# Accelerometer.net
KiCad netlist of a schematic drawn in Altium Designer
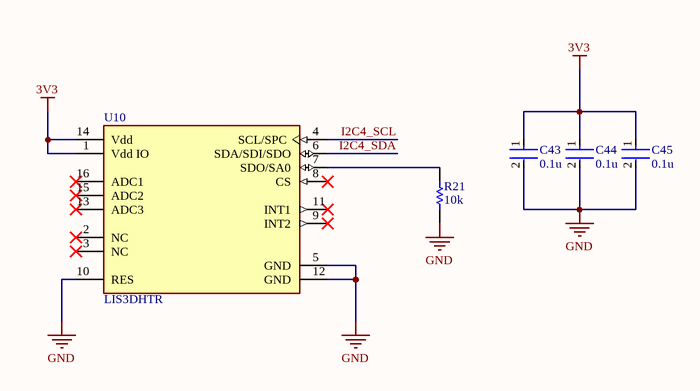
[diagram p0: Accelerometer.SchDoc]

(export (version "E")
  (design (tool "Eeschema 10.0.6"))
  (components
    (comp (ref "C43")
      (value "0.1u")
      (footprint "FP-C0603C-CF-MFG")
      (description "CAP CER 0.1UF 50V X7R 0603")
      (fields (field (name "TOLERANCE") "0.1") (field (name "MANUFACTURER") "KEMET"))
      (libsource (lib "Altium Content Vault") (part "b4654b650e69147ec39a6b967a45e02"))
    )
    (comp (ref "C44")
      (value "0.1u")
      (footprint "FP-C0603C-CF-MFG")
      (description "CAP CER 0.1UF 50V X7R 0603")
      (fields (field (name "TOLERANCE") "0.1") (field (name "MANUFACTURER") "KEMET"))
      (libsource (lib "Altium Content Vault") (part "b4654b650e69147ec39a6b967a45e02"))
    )
    (comp (ref "C45")
      (value "0.1u")
      (footprint "FP-C0603C-CF-MFG")
      (description "CAP CER 0.1UF 50V X7R 0603")
      (fields (field (name "TOLERANCE") "0.1") (field (name "MANUFACTURER") "KEMET"))
      (libsource (lib "Altium Content Vault") (part "b4654b650e69147ec39a6b967a45e02"))
    )
    (comp (ref "R21")
      (value "10k")
      (footprint "RESC1609X50X30NL8T20")
      (description "Chip Resistor, 10 KOhm, +/- 1%, 100 mW, -55 to 155 degC, 0603 (1608 Metric), RoHS, Tape and Reel")
      (fields (field (name "MANUFACTURER") "Vishay Semiconductor"))
      (libsource (lib "Altium Content Vault") (part "RES-2"))
    )
    (comp (ref "U10")
      (value "LIS3DHTR")
      (footprint "FP-LGA-16-7983231-MFG")
      (description "ACCEL 2-16G I2C/SPI 16LGA")
      (libsource (lib "Altium Content Vault") (part "1e4772b22d749da4b53766bc623c8dd"))
    )
  )
  (nets
    (net (code "1") (name "/I2C4_SCL") (class "Default")
      (node (ref "U10") (pin "4") (pinfunction "SCL/SPC_4") (pintype "input"))
    )
    (net (code "2") (name "/I2C4_SDA") (class "Default")
      (node (ref "U10") (pin "6") (pinfunction "SDA/SDI/SDO_6") (pintype "bidirectional"))
    )
    (net (code "3") (name "3V3") (class "Default")
      (node (ref "C43") (pin "1") (pinfunction "1_1") (pintype "passive"))
      (node (ref "C44") (pin "1") (pinfunction "1_1") (pintype "passive"))
      (node (ref "C45") (pin "1") (pinfunction "1_1") (pintype "passive"))
      (node (ref "U10") (pin "1") (pinfunction "Vdd_IO_1") (pintype "power_in"))
      (node (ref "U10") (pin "14") (pinfunction "Vdd_14") (pintype "power_in"))
    )
    (net (code "4") (name "GND") (class "Default")
      (node (ref "C43") (pin "2") (pinfunction "2_2") (pintype "passive"))
      (node (ref "C44") (pin "2") (pinfunction "2_2") (pintype "passive"))
      (node (ref "C45") (pin "2") (pinfunction "2_2") (pintype "passive"))
      (node (ref "R21") (pin "1") (pinfunction "1_1") (pintype "passive"))
      (node (ref "U10") (pin "10") (pinfunction "RES_10") (pintype "passive"))
      (node (ref "U10") (pin "12") (pinfunction "GND_12") (pintype "power_in"))
      (node (ref "U10") (pin "5") (pinfunction "GND_5") (pintype "power_in"))
    )
    (net (code "5") (name "Net-(U10-SDO{slash}SA0)") (class "Default")
      (node (ref "R21") (pin "2") (pinfunction "2_2") (pintype "passive"))
      (node (ref "U10") (pin "7") (pinfunction "SDO/SA0_7") (pintype "bidirectional"))
    )
    (net (code "6") (name "unconnected-(U10-ADC1-Pad16)") (class "Default")
      (node (ref "U10") (pin "16") (pinfunction "ADC1_16") (pintype "passive+no_connect"))
    )
    (net (code "7") (name "unconnected-(U10-ADC2-Pad15)") (class "Default")
      (node (ref "U10") (pin "15") (pinfunction "ADC2_15") (pintype "passive+no_connect"))
    )
    (net (code "8") (name "unconnected-(U10-ADC3-Pad13)") (class "Default")
      (node (ref "U10") (pin "13") (pinfunction "ADC3_13") (pintype "passive+no_connect"))
    )
    (net (code "9") (name "unconnected-(U10-CS-Pad8)") (class "Default")
      (node (ref "U10") (pin "8") (pinfunction "CS_8") (pintype "input+no_connect"))
    )
    (net (code "10") (name "unconnected-(U10-INT1-Pad11)") (class "Default")
      (node (ref "U10") (pin "11") (pinfunction "INT1_11") (pintype "output+no_connect"))
    )
    (net (code "11") (name "unconnected-(U10-INT2-Pad9)") (class "Default")
      (node (ref "U10") (pin "9") (pinfunction "INT2_9") (pintype "output+no_connect"))
    )
    (net (code "12") (name "unconnected-(U10-NC-Pad2)") (class "Default")
      (node (ref "U10") (pin "2") (pinfunction "NC_2") (pintype "passive+no_connect"))
    )
    (net (code "13") (name "unconnected-(U10-NC-Pad3)") (class "Default")
      (node (ref "U10") (pin "3") (pinfunction "NC_3") (pintype "passive+no_connect"))
    )
  )
)
